# EIS_Main.net
KiCad netlist of a schematic drawn in Altium Designer
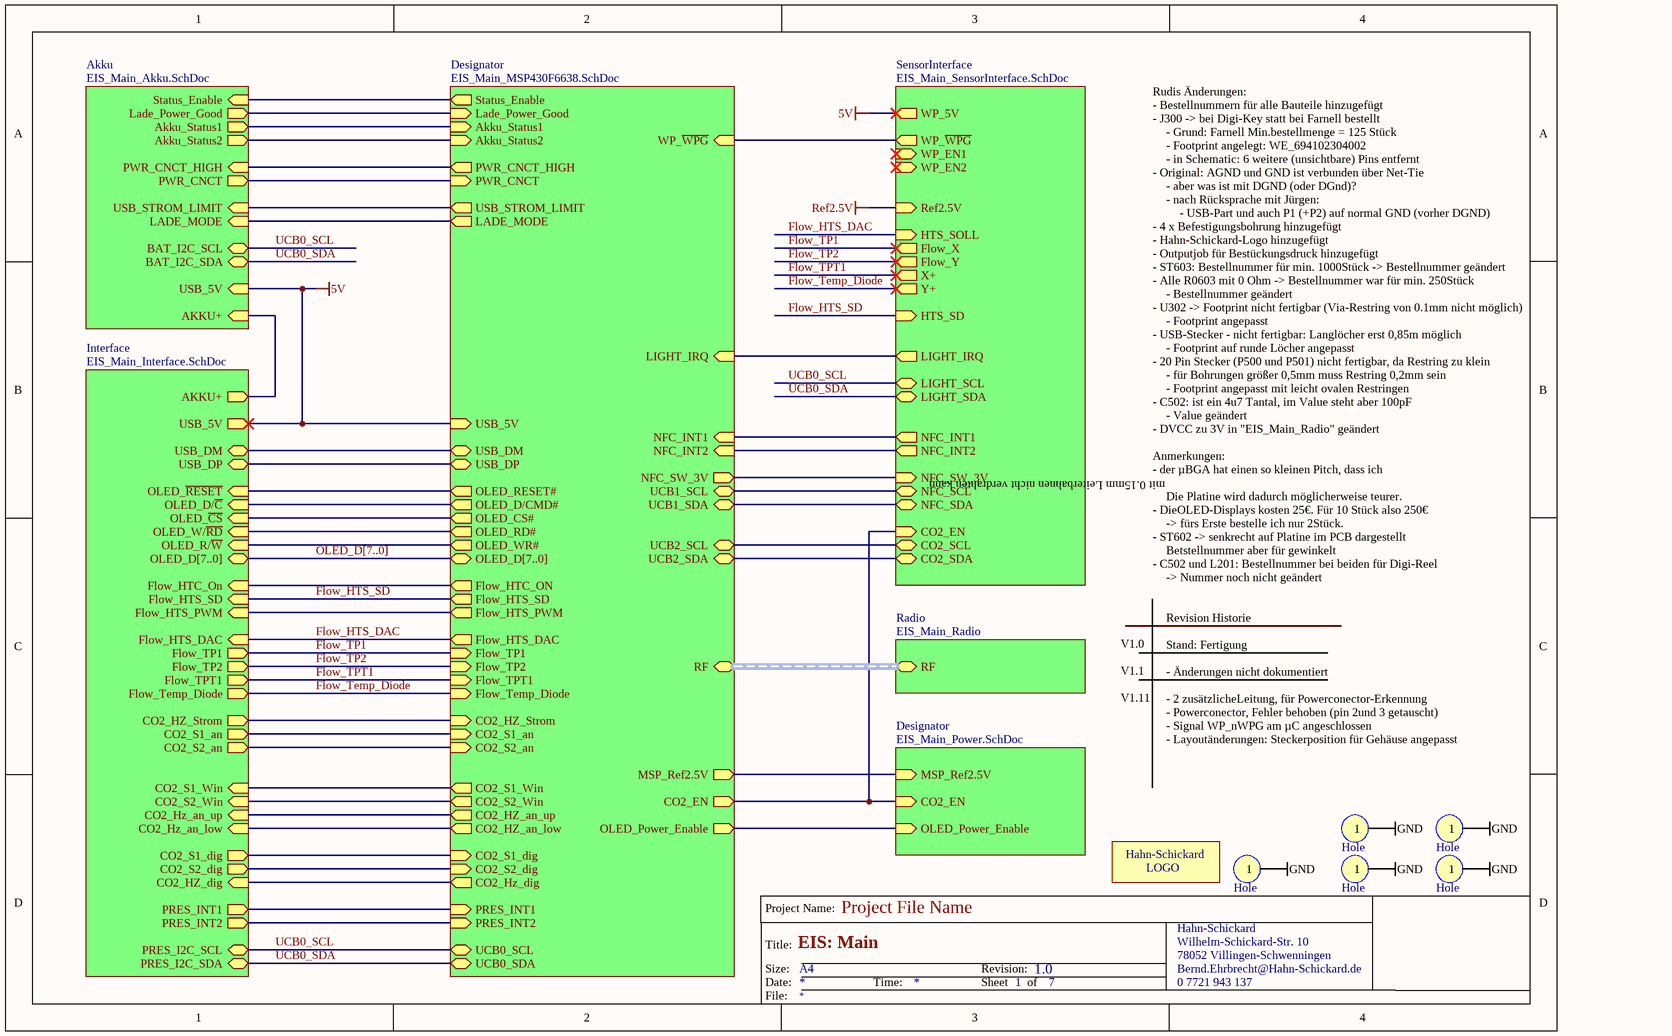
[diagram p0: EIS_Main.SchDoc]

(export (version "E")
  (design (tool "Eeschema 10.0.6"))
  (components
    (comp (ref "LOGO1")
      (value "Hahn-Schickard-Logo")
      (footprint "Hahn-Schickard-LOGO_klein")
      (description "Hahn-Schickard Logo als Footprint")
      (libsource (lib "RudiSchlibAllg") (part "Hahn-Schickard-Logo"))
    )
    (comp (ref "X1")
      (value "Hole")
      (footprint "Hole_2mm")
      (description "Durchkontaktierung d=4mm")
      (libsource (lib "RudiSchlibAllg") (part "Hole"))
    )
    (comp (ref "X2")
      (value "Hole")
      (footprint "Hole_2mm")
      (description "Durchkontaktierung d=4mm")
      (libsource (lib "RudiSchlibAllg") (part "Hole"))
    )
    (comp (ref "X3")
      (value "Hole")
      (footprint "Hole_2mm")
      (description "Durchkontaktierung d=4mm")
      (libsource (lib "RudiSchlibAllg") (part "Hole"))
    )
    (comp (ref "X4")
      (value "Hole")
      (footprint "Hole_2mm")
      (description "Durchkontaktierung d=4mm")
      (libsource (lib "RudiSchlibAllg") (part "Hole"))
    )
    (comp (ref "X5")
      (value "Hole")
      (footprint "Hole_2mm")
      (description "Durchkontaktierung d=4mm")
      (libsource (lib "RudiSchlibAllg") (part "Hole"))
    )
  )
  (nets
    (net (code "64") (name "GND") (class "Default")
      (node (ref "X1") (pin "1") (pinfunction "1_1") (pintype "passive"))
      (node (ref "X2") (pin "1") (pinfunction "1_1") (pintype "passive"))
      (node (ref "X3") (pin "1") (pinfunction "1_1") (pintype "passive"))
      (node (ref "X4") (pin "1") (pinfunction "1_1") (pintype "passive"))
      (node (ref "X5") (pin "1") (pinfunction "1_1") (pintype "passive"))
    )
  )
)
